# WX0_011_105DL.net
KiCad netlist of a schematic drawn in Altium Designer
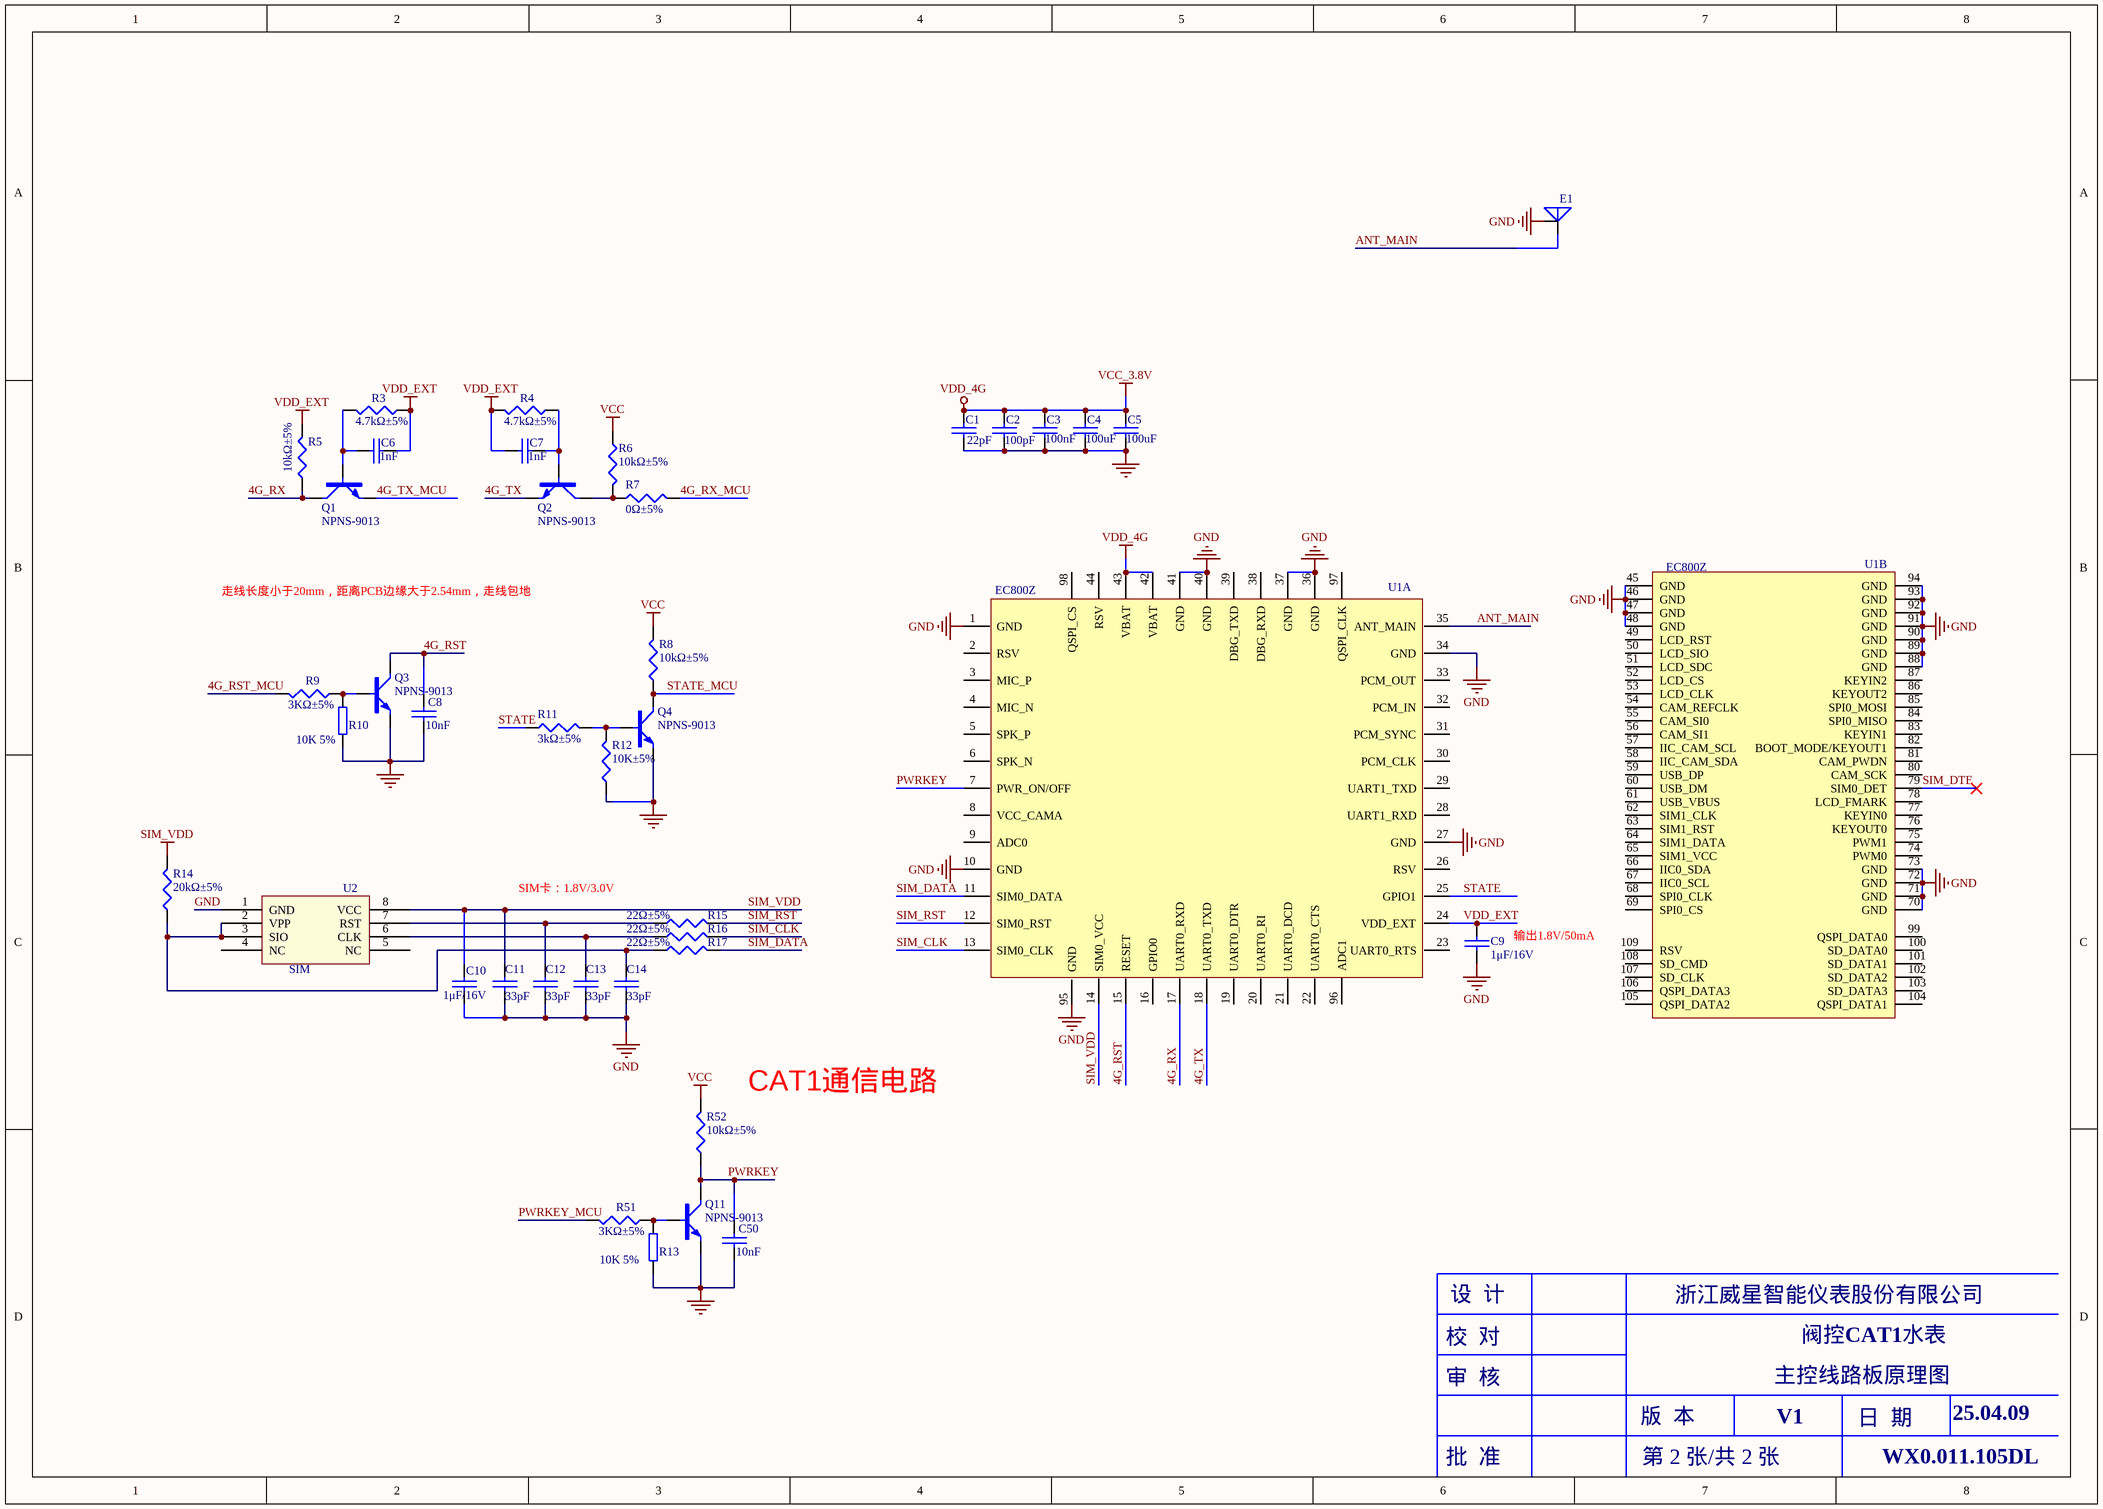
[diagram p0: WX0.011.105DL.SchDoc]

(export (version "E")
  (design (tool "Eeschema 10.0.6"))
  (components
    (comp (ref "C1")
      (value "22pF")
      (footprint "CAP0603")
      (description "贴片电容,22pF±5%/50V,NP0,国巨")
      (fields (field (name "PART NUMBER") "101020103-0009") (field (name "MANUFACTURER") "国巨"))
      (libsource (lib "Devices") (part "CAP"))
    )
    (comp (ref "C2")
      (value "100pF")
      (footprint "CAP0603")
      (description "贴片电容,100pF±10%/50V,NP0,国巨")
      (fields (field (name "PART NUMBER") "101020103-0010") (field (name "MANUFACTURER") "国巨"))
      (libsource (lib "Devices") (part "CAP"))
    )
    (comp (ref "C3")
      (value "100nF")
      (footprint "CAP0603")
      (description "贴片电容,100nF±10%/50V,X7R,国巨")
      (fields (field (name "PART NUMBER") "101020103-0021") (field (name "MANUFACTURER") "国巨"))
      (libsource (lib "Devices") (part "CAP"))
    )
    (comp (ref "C4")
      (value "100uF")
      (footprint "GRM1206")
      (description "贴片电容,100uF±20%/6.3V,X5R,村田")
      (fields (field (name "PART NUMBER") "101020101-0020") (field (name "MANUFACTURER") "村田"))
      (libsource (lib "Devices") (part "CAP"))
    )
    (comp (ref "C5")
      (value "100uF")
      (footprint "GRM1206")
      (description "贴片电容,100uF±20%/6.3V,X5R,村田")
      (fields (field (name "PART NUMBER") "101020101-0020") (field (name "MANUFACTURER") "村田"))
      (libsource (lib "Devices") (part "CAP"))
    )
    (comp (ref "C6")
      (value "1nF")
      (footprint "CAP0603")
      (description "贴片电容,1nF±10%/50V,X7R,国巨")
      (fields (field (name "PART NUMBER") "101020103-0022") (field (name "MANUFACTURER") "国巨"))
      (libsource (lib "Devices") (part "CAP"))
    )
    (comp (ref "C7")
      (value "1nF")
      (footprint "CAP0603")
      (description "贴片电容,1nF±10%/50V,X7R,国巨")
      (fields (field (name "PART NUMBER") "101020103-0022") (field (name "MANUFACTURER") "国巨"))
      (libsource (lib "Devices") (part "CAP"))
    )
    (comp (ref "C8")
      (value "10nF")
      (footprint "CAP0603")
      (description "贴片电容,10nF±10%/50V,X7R,国巨")
      (fields (field (name "PART NUMBER") "101020103-0007") (field (name "MANUFACTURER") "国巨"))
      (libsource (lib "Devices") (part "CAP"))
    )
    (comp (ref "C9")
      (value "1μF/16V")
      (footprint "CAP0603")
      (description "贴片电容,1μF±10%/16V,X7R,国巨")
      (fields (field (name "PART NUMBER") "101020103-0003") (field (name "MANUFACTURER") "国巨"))
      (libsource (lib "Devices") (part "CAP"))
    )
    (comp (ref "C10")
      (value "1μF/16V")
      (footprint "CAP0603")
      (description "贴片电容,1μF±10%/16V,X7R,国巨")
      (fields (field (name "PART NUMBER") "101020103-0003") (field (name "MANUFACTURER") "国巨"))
      (libsource (lib "Devices") (part "CAP"))
    )
    (comp (ref "C11")
      (value "33pF")
      (footprint "CAP0603")
      (description "贴片电容,33pF±10%/50V,NP0,国巨")
      (fields (field (name "PART NUMBER") "101020103-0027") (field (name "MANUFACTURER") "国巨"))
      (libsource (lib "Devices") (part "CAP"))
    )
    (comp (ref "C12")
      (value "33pF")
      (footprint "CAP0603")
      (description "贴片电容,33pF±10%/50V,NP0,国巨")
      (fields (field (name "PART NUMBER") "101020103-0027") (field (name "MANUFACTURER") "国巨"))
      (libsource (lib "Devices") (part "CAP"))
    )
    (comp (ref "C13")
      (value "33pF")
      (footprint "CAP0603")
      (description "贴片电容,33pF±10%/50V,NP0,国巨")
      (fields (field (name "PART NUMBER") "101020103-0027") (field (name "MANUFACTURER") "国巨"))
      (libsource (lib "Devices") (part "CAP"))
    )
    (comp (ref "C14")
      (value "33pF")
      (footprint "CAP0603")
      (description "贴片电容,33pF±10%/50V,NP0,国巨")
      (fields (field (name "PART NUMBER") "101020103-0027") (field (name "MANUFACTURER") "国巨"))
      (libsource (lib "Devices") (part "CAP"))
    )
    (comp (ref "C50")
      (value "10nF")
      (footprint "CAP0603")
      (description "贴片电容,10nF±10%/50V,X7R,国巨")
      (fields (field (name "PART NUMBER") "101020103-0007") (field (name "MANUFACTURER") "国巨"))
      (libsource (lib "Devices") (part "CAP"))
    )
    (comp (ref "E1")
      (value "ANTENNA_3")
      (footprint "天线")
      (description "外置天线焊盘（固定孔）")
      (libsource (lib "Devices") (part "ANTENNA_3"))
    )
    (comp (ref "Q1")
      (value "NPNS-9013")
      (footprint "SOT-23")
      (description "9013,NPN,SOT-23,长电,S9013")
      (fields (field (name "PART NUMBER") "101040201-0002"))
      (libsource (lib "Database_Libs2") (part "03_NPNS-9013"))
    )
    (comp (ref "Q2")
      (value "NPNS-9013")
      (footprint "SOT-23")
      (description "9013,NPN,SOT-23,长电,S9013")
      (fields (field (name "PART NUMBER") "101040201-0002"))
      (libsource (lib "Database_Libs2") (part "03_NPNS-9013"))
    )
    (comp (ref "Q3")
      (value "NPNS-9013")
      (footprint "SOT-23")
      (description "9013,NPN,SOT-23,长电,S9013")
      (fields (field (name "PART NUMBER") "101040201-0002"))
      (libsource (lib "Database_Libs2") (part "03_NPNS-9013"))
    )
    (comp (ref "Q4")
      (value "NPNS-9013")
      (footprint "SOT-23")
      (description "9013,NPN,SOT-23,长电,S9013")
      (fields (field (name "PART NUMBER") "101040201-0002"))
      (libsource (lib "Database_Libs2") (part "03_NPNS-9013"))
    )
    (comp (ref "Q11")
      (value "NPNS-9013")
      (footprint "SOT-23")
      (description "9013,NPN,SOT-23,长电,S9013")
      (fields (field (name "PART NUMBER") "101040201-0002"))
      (libsource (lib "Database_Libs2") (part "03_NPNS-9013"))
    )
    (comp (ref "R3")
      (value "4.7kΩ±5%")
      (footprint "RES0603")
      (description "贴片电阻,4.7kΩ±5%,1/10W,100ppm/℃,国巨")
      (fields (field (name "PART NUMBER") "101010103-0042") (field (name "MANUFACTURER") "国巨"))
      (libsource (lib "Devices") (part "RES1"))
    )
    (comp (ref "R4")
      (value "4.7kΩ±5%")
      (footprint "RES0603")
      (description "贴片电阻,4.7kΩ±5%,1/10W,100ppm/℃,国巨")
      (fields (field (name "PART NUMBER") "101010103-0042") (field (name "MANUFACTURER") "国巨"))
      (libsource (lib "Devices") (part "RES1"))
    )
    (comp (ref "R5")
      (value "10kΩ±5%")
      (footprint "RES0603")
      (description "贴片电阻,10kΩ±5%,1/10W,100ppm/℃,国巨")
      (fields (field (name "PART NUMBER") "101010103-0003") (field (name "MANUFACTURER") "国巨"))
      (libsource (lib "Devices") (part "RES1"))
    )
    (comp (ref "R6")
      (value "10kΩ±5%")
      (footprint "RES0603")
      (description "贴片电阻,10kΩ±5%,1/10W,100ppm/℃,国巨")
      (fields (field (name "PART NUMBER") "101010103-0003") (field (name "MANUFACTURER") "国巨"))
      (libsource (lib "Devices") (part "RES1"))
    )
    (comp (ref "R7")
      (value "0Ω±5%")
      (footprint "RES0603")
      (description "贴片电阻,0Ω±5%,1/10W,100ppm/℃,国巨")
      (fields (field (name "PART NUMBER") "101010103-0001") (field (name "MANUFACTURER") "国巨"))
      (libsource (lib "Devices") (part "RES1"))
    )
    (comp (ref "R8")
      (value "10kΩ±5%")
      (footprint "RES0603")
      (description "贴片电阻,10kΩ±5%,1/10W,100ppm/℃,国巨")
      (fields (field (name "PART NUMBER") "101010103-0003") (field (name "MANUFACTURER") "国巨"))
      (libsource (lib "Devices") (part "RES1"))
    )
    (comp (ref "R9")
      (value "3KΩ±5%")
      (footprint "RES0603")
      (description "贴片电阻,4.7kΩ±5%,1/10W,100ppm/℃,国巨")
      (fields (field (name "PART NUMBER") "101010103-0042") (field (name "MANUFACTURER") "国巨"))
      (libsource (lib "Devices") (part "RES1"))
    )
    (comp (ref "R10")
      (value "10K 5%")
      (footprint "RES0603")
      (description "国巨,±5%,0603,,155 ℃,-55 ℃,RC0603JR-0710KL,无铅,200 ppm/℃,1/10W,,10K")
      (fields (field (name "PART NUMBER") "101010103-0003"))
      (libsource (lib "Database_Libs2") (part "RC03J_10K"))
    )
    (comp (ref "R11")
      (value "3kΩ±5%")
      (footprint "RES0603")
      (description "贴片电阻,4.7kΩ±5%,1/10W,100ppm/℃,国巨")
      (fields (field (name "PART NUMBER") "101010103-0042") (field (name "MANUFACTURER") "国巨"))
      (libsource (lib "Devices") (part "RES1"))
    )
    (comp (ref "R12")
      (value "10K±5%")
      (footprint "RES0603")
      (description "贴片电阻，47K,±5%,1/10W,0603,国巨,RC0603JR-0747KL")
      (fields (field (name "PART NUMBER") "101010103-0012") (field (name "MANUFACTURER") "国巨"))
      (libsource (lib "Devices") (part "RES1"))
    )
    (comp (ref "R13")
      (value "10K 5%")
      (footprint "RES0603")
      (description "国巨,±5%,0603,,155 ℃,-55 ℃,RC0603JR-0710KL,无铅,200 ppm/℃,1/10W,,10K")
      (fields (field (name "PART NUMBER") "101010103-0003"))
      (libsource (lib "Database_Libs2") (part "RC03J_10K"))
    )
    (comp (ref "R14")
      (value "20kΩ±5%")
      (footprint "RES0603")
      (description "贴片电阻,4.7kΩ±5%,1/10W,100ppm/℃,国巨")
      (fields (field (name "PART NUMBER") "101010103-0042") (field (name "MANUFACTURER") "国巨"))
      (libsource (lib "Devices") (part "RES1"))
    )
    (comp (ref "R15")
      (value "22Ω±5%")
      (footprint "RES0603")
      (description "贴片电阻,22Ω±5%,1/10W,100ppm/℃,国巨")
      (fields (field (name "PART NUMBER") "101010103-0009") (field (name "MANUFACTURER") "国巨"))
      (libsource (lib "Devices") (part "RES1"))
    )
    (comp (ref "R16")
      (value "22Ω±5%")
      (footprint "RES0603")
      (description "贴片电阻,22Ω±5%,1/10W,100ppm/℃,国巨")
      (fields (field (name "PART NUMBER") "101010103-0009") (field (name "MANUFACTURER") "国巨"))
      (libsource (lib "Database_Libs2") (part "RES1"))
    )
    (comp (ref "R17")
      (value "22Ω±5%")
      (footprint "RES0603")
      (description "贴片电阻,22Ω±5%,1/10W,100ppm/℃,国巨")
      (fields (field (name "PART NUMBER") "101010103-0009") (field (name "MANUFACTURER") "国巨"))
      (libsource (lib "Devices") (part "RES1"))
    )
    (comp (ref "R51")
      (value "3KΩ±5%")
      (footprint "RES0603")
      (description "贴片电阻,4.7kΩ±5%,1/10W,100ppm/℃,国巨")
      (fields (field (name "PART NUMBER") "101010103-0042") (field (name "MANUFACTURER") "国巨"))
      (libsource (lib "Devices") (part "RES1"))
    )
    (comp (ref "R52")
      (value "10kΩ±5%")
      (footprint "RES0603")
      (description "贴片电阻,10kΩ±5%,1/10W,100ppm/℃,国巨")
      (fields (field (name "PART NUMBER") "101010103-0003") (field (name "MANUFACTURER") "国巨"))
      (libsource (lib "Devices") (part "RES1"))
    )
    (comp (ref "U1")
      (value "EC800Z")
      (footprint "MOD_ML307X_LGA109P")
      (description "集成电路,中国移动，ML307R")
      (fields (field (name "MANUFACTURER") "中国移动"))
      (libsource (lib "Devices") (part "MOD_ML307X_LGA109P"))
    )
    (comp (ref "U2")
      (value "SIM")
      (footprint "SIMIC")
      (description "集成电路,ESIM,杭州电信")
      (fields (field (name "PART NUMBER") "101050101-0120") (field (name "MANUFACTURER") "电信"))
      (libsource (lib "Devices") (part "ESIM"))
    )
  )
  (nets
    (net (code "1") (name "/4G_RST") (class "Default")
      (node (ref "C8") (pin "2") (pinfunction "2_2") (pintype "passive"))
      (node (ref "Q3") (pin "3") (pinfunction "C_3") (pintype "passive"))
      (node (ref "U1") (pin "15") (pinfunction "RESET_15") (pintype "passive"))
    )
    (net (code "2") (name "/4G_RST_MCU") (class "Default")
      (node (ref "R9") (pin "2") (pinfunction "2_2") (pintype "passive"))
    )
    (net (code "3") (name "/4G_RX") (class "Default")
      (node (ref "Q1") (pin "3") (pinfunction "C_3") (pintype "passive"))
      (node (ref "R5") (pin "1") (pinfunction "1_1") (pintype "passive"))
      (node (ref "U1") (pin "17") (pinfunction "UART0_RXD_17") (pintype "passive"))
    )
    (net (code "4") (name "/4G_RX_MCU") (class "Default")
      (node (ref "R7") (pin "2") (pinfunction "2_2") (pintype "passive"))
    )
    (net (code "5") (name "/4G_TX") (class "Default")
      (node (ref "Q2") (pin "2") (pinfunction "E_2") (pintype "passive"))
      (node (ref "U1") (pin "18") (pinfunction "UART0_TXD_18") (pintype "passive"))
    )
    (net (code "6") (name "/4G_TX_MCU") (class "Default")
      (node (ref "Q1") (pin "2") (pinfunction "E_2") (pintype "passive"))
    )
    (net (code "7") (name "/ANT_MAIN") (class "Default")
      (node (ref "E1") (pin "1") (pinfunction "A_1") (pintype "passive"))
      (node (ref "U1") (pin "35") (pinfunction "ANT_MAIN_35") (pintype "passive"))
    )
    (net (code "8") (name "/PWRKEY") (class "Default")
      (node (ref "C50") (pin "2") (pinfunction "2_2") (pintype "passive"))
      (node (ref "Q11") (pin "3") (pinfunction "C_3") (pintype "passive"))
      (node (ref "R52") (pin "1") (pinfunction "1_1") (pintype "passive"))
      (node (ref "U1") (pin "7") (pinfunction "PWR_ON/OFF_7") (pintype "passive"))
    )
    (net (code "9") (name "/PWRKEY_MCU") (class "Default")
      (node (ref "R51") (pin "2") (pinfunction "2_2") (pintype "passive"))
    )
    (net (code "10") (name "/SIM_CLK") (class "Default")
      (node (ref "R16") (pin "2") (pinfunction "2_2") (pintype "passive"))
      (node (ref "U1") (pin "13") (pinfunction "SIM0_CLK_13") (pintype "passive"))
    )
    (net (code "11") (name "/SIM_DATA") (class "Default")
      (node (ref "R17") (pin "2") (pinfunction "2_2") (pintype "passive"))
      (node (ref "U1") (pin "11") (pinfunction "SIM0_DATA_11") (pintype "passive"))
    )
    (net (code "12") (name "/SIM_DTE") (class "Default")
      (node (ref "U1") (pin "79") (pinfunction "SIM0_DET_79") (pintype "passive+no_connect"))
    )
    (net (code "13") (name "/SIM_RST") (class "Default")
      (node (ref "R15") (pin "2") (pinfunction "2_2") (pintype "passive"))
      (node (ref "U1") (pin "12") (pinfunction "SIM0_RST_12") (pintype "passive"))
    )
    (net (code "14") (name "/STATE") (class "Default")
      (node (ref "R11") (pin "1") (pinfunction "1_1") (pintype "passive"))
      (node (ref "U1") (pin "25") (pinfunction "GPIO1_25") (pintype "passive"))
    )
    (net (code "15") (name "/STATE_MCU") (class "Default")
      (node (ref "Q4") (pin "3") (pinfunction "C_3") (pintype "passive"))
      (node (ref "R8") (pin "1") (pinfunction "1_1") (pintype "passive"))
    )
    (net (code "16") (name "GND") (class "Default")
      (node (ref "C1") (pin "1") (pinfunction "1_1") (pintype "passive"))
      (node (ref "C10") (pin "1") (pinfunction "1_1") (pintype "passive"))
      (node (ref "C11") (pin "1") (pinfunction "1_1") (pintype "passive"))
      (node (ref "C12") (pin "1") (pinfunction "1_1") (pintype "passive"))
      (node (ref "C13") (pin "1") (pinfunction "1_1") (pintype "passive"))
      (node (ref "C14") (pin "1") (pinfunction "1_1") (pintype "passive"))
      (node (ref "C2") (pin "1") (pinfunction "1_1") (pintype "passive"))
      (node (ref "C3") (pin "1") (pinfunction "1_1") (pintype "passive"))
      (node (ref "C4") (pin "1") (pinfunction "1_1") (pintype "passive"))
      (node (ref "C5") (pin "1") (pinfunction "1_1") (pintype "passive"))
      (node (ref "C50") (pin "1") (pinfunction "1_1") (pintype "passive"))
      (node (ref "C8") (pin "1") (pinfunction "1_1") (pintype "passive"))
      (node (ref "C9") (pin "1") (pinfunction "1_1") (pintype "passive"))
      (node (ref "E1") (pin "2") (pinfunction "2_2") (pintype "passive"))
      (node (ref "Q11") (pin "2") (pinfunction "E_2") (pintype "passive"))
      (node (ref "Q3") (pin "2") (pinfunction "E_2") (pintype "passive"))
      (node (ref "Q4") (pin "2") (pinfunction "E_2") (pintype "passive"))
      (node (ref "R10") (pin "1") (pinfunction "1_1") (pintype "passive"))
      (node (ref "R12") (pin "1") (pinfunction "1_1") (pintype "passive"))
      (node (ref "R13") (pin "1") (pinfunction "1_1") (pintype "passive"))
      (node (ref "U1") (pin "1") (pinfunction "GND_1") (pintype "passive"))
      (node (ref "U1") (pin "10") (pinfunction "GND_10") (pintype "passive"))
      (node (ref "U1") (pin "27") (pinfunction "GND_27") (pintype "passive"))
      (node (ref "U1") (pin "34") (pinfunction "GND_34") (pintype "passive"))
      (node (ref "U1") (pin "36") (pinfunction "GND_36") (pintype "passive"))
      (node (ref "U1") (pin "37") (pinfunction "GND_37") (pintype "passive"))
      (node (ref "U1") (pin "40") (pinfunction "GND_40") (pintype "passive"))
      (node (ref "U1") (pin "41") (pinfunction "GND_41") (pintype "passive"))
      (node (ref "U1") (pin "45") (pinfunction "GND_45") (pintype "passive"))
      (node (ref "U1") (pin "46") (pinfunction "GND_46") (pintype "passive"))
      (node (ref "U1") (pin "47") (pinfunction "GND_47") (pintype "passive"))
      (node (ref "U1") (pin "48") (pinfunction "GND_48") (pintype "passive"))
      (node (ref "U1") (pin "70") (pinfunction "GND_70") (pintype "passive"))
      (node (ref "U1") (pin "71") (pinfunction "GND_71") (pintype "passive"))
      (node (ref "U1") (pin "72") (pinfunction "GND_72") (pintype "passive"))
      (node (ref "U1") (pin "73") (pinfunction "GND_73") (pintype "passive"))
      (node (ref "U1") (pin "88") (pinfunction "GND_88") (pintype "passive"))
      (node (ref "U1") (pin "89") (pinfunction "GND_89") (pintype "passive"))
      (node (ref "U1") (pin "90") (pinfunction "GND_90") (pintype "passive"))
      (node (ref "U1") (pin "91") (pinfunction "GND_91") (pintype "passive"))
      (node (ref "U1") (pin "92") (pinfunction "GND_92") (pintype "passive"))
      (node (ref "U1") (pin "93") (pinfunction "GND_93") (pintype "passive"))
      (node (ref "U1") (pin "94") (pinfunction "GND_94") (pintype "passive"))
      (node (ref "U1") (pin "95") (pinfunction "GND_95") (pintype "passive"))
      (node (ref "U2") (pin "1") (pinfunction "GND_1") (pintype "passive"))
    )
    (net (code "17") (name "Net-(Q1-B)") (class "Default")
      (node (ref "C6") (pin "1") (pinfunction "1_1") (pintype "passive"))
      (node (ref "Q1") (pin "1") (pinfunction "B_1") (pintype "passive"))
      (node (ref "R3") (pin "2") (pinfunction "2_2") (pintype "passive"))
    )
    (net (code "18") (name "Net-(Q2-B)") (class "Default")
      (node (ref "C7") (pin "2") (pinfunction "2_2") (pintype "passive"))
      (node (ref "Q2") (pin "1") (pinfunction "B_1") (pintype "passive"))
      (node (ref "R4") (pin "1") (pinfunction "1_1") (pintype "passive"))
    )
    (net (code "19") (name "Net-(Q2-C)") (class "Default")
      (node (ref "Q2") (pin "3") (pinfunction "C_3") (pintype "passive"))
      (node (ref "R6") (pin "2") (pinfunction "2_2") (pintype "passive"))
      (node (ref "R7") (pin "1") (pinfunction "1_1") (pintype "passive"))
    )
    (net (code "20") (name "Net-(Q3-B)") (class "Default")
      (node (ref "Q3") (pin "1") (pinfunction "B_1") (pintype "passive"))
      (node (ref "R10") (pin "2") (pinfunction "2_2") (pintype "passive"))
      (node (ref "R9") (pin "1") (pinfunction "1_1") (pintype "passive"))
    )
    (net (code "21") (name "Net-(Q4-B)") (class "Default")
      (node (ref "Q4") (pin "1") (pinfunction "B_1") (pintype "passive"))
      (node (ref "R11") (pin "2") (pinfunction "2_2") (pintype "passive"))
      (node (ref "R12") (pin "2") (pinfunction "2_2") (pintype "passive"))
    )
    (net (code "22") (name "Net-(Q11-B)") (class "Default")
      (node (ref "Q11") (pin "1") (pinfunction "B_1") (pintype "passive"))
      (node (ref "R13") (pin "2") (pinfunction "2_2") (pintype "passive"))
      (node (ref "R51") (pin "1") (pinfunction "1_1") (pintype "passive"))
    )
    (net (code "23") (name "Net-(U2-CLK)") (class "Default")
      (node (ref "C13") (pin "2") (pinfunction "2_2") (pintype "passive"))
      (node (ref "R16") (pin "1") (pinfunction "1_1") (pintype "passive"))
      (node (ref "U2") (pin "6") (pinfunction "CLK_6") (pintype "passive"))
    )
    (net (code "24") (name "Net-(U2-RST)") (class "Default")
      (node (ref "C12") (pin "2") (pinfunction "2_2") (pintype "passive"))
      (node (ref "R15") (pin "1") (pinfunction "1_1") (pintype "passive"))
      (node (ref "U2") (pin "7") (pinfunction "RST_7") (pintype "passive"))
    )
    (net (code "25") (name "Net-(U2-SIO)") (class "Default")
      (node (ref "C14") (pin "2") (pinfunction "2_2") (pintype "passive"))
      (node (ref "R14") (pin "1") (pinfunction "1_1") (pintype "passive"))
      (node (ref "R17") (pin "1") (pinfunction "1_1") (pintype "passive"))
      (node (ref "U2") (pin "2") (pinfunction "VPP_2") (pintype "passive"))
      (node (ref "U2") (pin "3") (pinfunction "SIO_3") (pintype "passive"))
    )
    (net (code "26") (name "SIM_VDD") (class "Default")
      (node (ref "C10") (pin "2") (pinfunction "2_2") (pintype "passive"))
      (node (ref "C11") (pin "2") (pinfunction "2_2") (pintype "passive"))
      (node (ref "R14") (pin "2") (pinfunction "2_2") (pintype "passive"))
      (node (ref "U1") (pin "14") (pinfunction "SIM0_VCC_14") (pintype "passive"))
      (node (ref "U2") (pin "8") (pinfunction "VCC_8") (pintype "passive"))
    )
    (net (code "27") (name "VCC") (class "Default")
      (node (ref "R52") (pin "2") (pinfunction "2_2") (pintype "passive"))
      (node (ref "R6") (pin "1") (pinfunction "1_1") (pintype "passive"))
      (node (ref "R8") (pin "2") (pinfunction "2_2") (pintype "passive"))
    )
    (net (code "28") (name "VCC_3.8V") (class "Default")
      (node (ref "C1") (pin "2") (pinfunction "2_2") (pintype "passive"))
      (node (ref "C2") (pin "2") (pinfunction "2_2") (pintype "passive"))
      (node (ref "C3") (pin "2") (pinfunction "2_2") (pintype "passive"))
      (node (ref "C4") (pin "2") (pinfunction "2_2") (pintype "passive"))
      (node (ref "C5") (pin "2") (pinfunction "2_2") (pintype "passive"))
      (node (ref "U1") (pin "42") (pinfunction "VBAT_42") (pintype "passive"))
      (node (ref "U1") (pin "43") (pinfunction "VBAT_43") (pintype "passive"))
    )
    (net (code "29") (name "VDD_EXT") (class "Default")
      (node (ref "C6") (pin "2") (pinfunction "2_2") (pintype "passive"))
      (node (ref "C7") (pin "1") (pinfunction "1_1") (pintype "passive"))
      (node (ref "C9") (pin "2") (pinfunction "2_2") (pintype "passive"))
      (node (ref "R3") (pin "1") (pinfunction "1_1") (pintype "passive"))
      (node (ref "R4") (pin "2") (pinfunction "2_2") (pintype "passive"))
      (node (ref "R5") (pin "2") (pinfunction "2_2") (pintype "passive"))
      (node (ref "U1") (pin "24") (pinfunction "VDD_EXT_24") (pintype "passive"))
    )
    (net (code "30") (name "unconnected-(U1A-ADC0-Pad9)") (class "Default")
      (node (ref "U1") (pin "9") (pinfunction "ADC0_9") (pintype "passive"))
    )
    (net (code "31") (name "unconnected-(U1A-ADC1-Pad96)") (class "Default")
      (node (ref "U1") (pin "96") (pinfunction "ADC1_96") (pintype "passive"))
    )
    (net (code "32") (name "unconnected-(U1A-DBG_RXD-Pad38)") (class "Default")
      (node (ref "U1") (pin "38") (pinfunction "DBG_RXD_38") (pintype "passive"))
    )
    (net (code "33") (name "unconnected-(U1A-DBG_TXD-Pad39)") (class "Default")
      (node (ref "U1") (pin "39") (pinfunction "DBG_TXD_39") (pintype "passive"))
    )
    (net (code "34") (name "unconnected-(U1A-GPIO0-Pad16)") (class "Default")
      (node (ref "U1") (pin "16") (pinfunction "GPIO0_16") (pintype "passive"))
    )
    (net (code "35") (name "unconnected-(U1A-MIC_N-Pad4)") (class "Default")
      (node (ref "U1") (pin "4") (pinfunction "MIC_N_4") (pintype "passive"))
    )
    (net (code "36") (name "unconnected-(U1A-MIC_P-Pad3)") (class "Default")
      (node (ref "U1") (pin "3") (pinfunction "MIC_P_3") (pintype "passive"))
    )
    (net (code "37") (name "unconnected-(U1A-PCM_CLK-Pad30)") (class "Default")
      (node (ref "U1") (pin "30") (pinfunction "PCM_CLK_30") (pintype "passive"))
    )
    (net (code "38") (name "unconnected-(U1A-PCM_IN-Pad32)") (class "Default")
      (node (ref "U1") (pin "32") (pinfunction "PCM_IN_32") (pintype "passive"))
    )
    (net (code "39") (name "unconnected-(U1A-PCM_OUT-Pad33)") (class "Default")
      (node (ref "U1") (pin "33") (pinfunction "PCM_OUT_33") (pintype "passive"))
    )
    (net (code "40") (name "unconnected-(U1A-PCM_SYNC-Pad31)") (class "Default")
      (node (ref "U1") (pin "31") (pinfunction "PCM_SYNC_31") (pintype "passive"))
    )
    (net (code "41") (name "unconnected-(U1A-QSPI_CLK-Pad97)") (class "Default")
      (node (ref "U1") (pin "97") (pinfunction "QSPI_CLK_97") (pintype "passive"))
    )
    (net (code "42") (name "unconnected-(U1A-QSPI_CS-Pad98)") (class "Default")
      (node (ref "U1") (pin "98") (pinfunction "QSPI_CS_98") (pintype "passive"))
    )
    (net (code "43") (name "unconnected-(U1A-RSV-Pad2)") (class "Default")
      (node (ref "U1") (pin "2") (pinfunction "RSV_2") (pintype "passive"))
    )
    (net (code "44") (name "unconnected-(U1A-RSV-Pad26)") (class "Default")
      (node (ref "U1") (pin "26") (pinfunction "RSV_26") (pintype "passive"))
    )
    (net (code "45") (name "unconnected-(U1A-RSV-Pad44)") (class "Default")
      (node (ref "U1") (pin "44") (pinfunction "RSV_44") (pintype "passive"))
    )
    (net (code "46") (name "unconnected-(U1A-SPK_N-Pad6)") (class "Default")
      (node (ref "U1") (pin "6") (pinfunction "SPK_N_6") (pintype "passive"))
    )
    (net (code "47") (name "unconnected-(U1A-SPK_P-Pad5)") (class "Default")
      (node (ref "U1") (pin "5") (pinfunction "SPK_P_5") (pintype "passive"))
    )
    (net (code "48") (name "unconnected-(U1A-UART0_CTS-Pad22)") (class "Default")
      (node (ref "U1") (pin "22") (pinfunction "UART0_CTS_22") (pintype "passive"))
    )
    (net (code "49") (name "unconnected-(U1A-UART0_DCD-Pad21)") (class "Default")
      (node (ref "U1") (pin "21") (pinfunction "UART0_DCD_21") (pintype "passive"))
    )
    (net (code "50") (name "unconnected-(U1A-UART0_DTR-Pad19)") (class "Default")
      (node (ref "U1") (pin "19") (pinfunction "UART0_DTR_19") (pintype "passive"))
    )
    (net (code "51") (name "unconnected-(U1A-UART0_RI-Pad20)") (class "Default")
      (node (ref "U1") (pin "20") (pinfunction "UART0_RI_20") (pintype "passive"))
    )
    (net (code "52") (name "unconnected-(U1A-UART0_RTS-Pad23)") (class "Default")
      (node (ref "U1") (pin "23") (pinfunction "UART0_RTS_23") (pintype "passive"))
    )
    (net (code "53") (name "unconnected-(U1A-UART1_RXD-Pad28)") (class "Default")
      (node (ref "U1") (pin "28") (pinfunction "UART1_RXD_28") (pintype "passive"))
    )
    (net (code "54") (name "unconnected-(U1A-UART1_TXD-Pad29)") (class "Default")
      (node (ref "U1") (pin "29") (pinfunction "UART1_TXD_29") (pintype "passive"))
    )
    (net (code "55") (name "unconnected-(U1A-VCC_CAMA-Pad8)") (class "Default")
      (node (ref "U1") (pin "8") (pinfunction "VCC_CAMA_8") (pintype "passive"))
    )
    (net (code "56") (name "unconnected-(U1B-BOOT_MODE{slash}KEYOUT1-Pad82)") (class "Default")
      (node (ref "U1") (pin "82") (pinfunction "BOOT_MODE/KEYOUT1_82") (pintype "passive"))
    )
    (net (code "57") (name "unconnected-(U1B-CAM_PWDN-Pad81)") (class "Default")
      (node (ref "U1") (pin "81") (pinfunction "CAM_PWDN_81") (pintype "passive"))
    )
    (net (code "58") (name "unconnected-(U1B-CAM_REFCLK-Pad54)") (class "Default")
      (node (ref "U1") (pin "54") (pinfunction "CAM_REFCLK_54") (pintype "passive"))
    )
    (net (code "59") (name "unconnected-(U1B-CAM_SCK-Pad80)") (class "Default")
      (node (ref "U1") (pin "80") (pinfunction "CAM_SCK_80") (pintype "passive"))
    )
    (net (code "60") (name "unconnected-(U1B-CAM_SI0-Pad55)") (class "Default")
      (node (ref "U1") (pin "55") (pinfunction "CAM_SI0_55") (pintype "passive"))
    )
    (net (code "61") (name "unconnected-(U1B-CAM_SI1-Pad56)") (class "Default")
      (node (ref "U1") (pin "56") (pinfunction "CAM_SI1_56") (pintype "passive"))
    )
    (net (code "62") (name "unconnected-(U1B-IIC0_SCL-Pad67)") (class "Default")
      (node (ref "U1") (pin "67") (pinfunction "IIC0_SCL_67") (pintype "passive"))
    )
    (net (code "63") (name "unconnected-(U1B-IIC0_SDA-Pad66)") (class "Default")
      (node (ref "U1") (pin "66") (pinfunction "IIC0_SDA_66") (pintype "passive"))
    )
    (net (code "64") (name "unconnected-(U1B-IIC_CAM_SCL-Pad57)") (class "Default")
      (node (ref "U1") (pin "57") (pinfunction "IIC_CAM_SCL_57") (pintype "passive"))
    )
    (net (code "65") (name "unconnected-(U1B-IIC_CAM_SDA-Pad58)") (class "Default")
      (node (ref "U1") (pin "58") (pinfunction "IIC_CAM_SDA_58") (pintype "passive"))
    )
    (net (code "66") (name "unconnected-(U1B-KEYIN0-Pad77)") (class "Default")
      (node (ref "U1") (pin "77") (pinfunction "KEYIN0_77") (pintype "passive"))
    )
    (net (code "67") (name "unconnected-(U1B-KEYIN1-Pad83)") (class "Default")
      (node (ref "U1") (pin "83") (pinfunction "KEYIN1_83") (pintype "passive"))
    )
    (net (code "68") (name "unconnected-(U1B-KEYIN2-Pad87)") (class "Default")
      (node (ref "U1") (pin "87") (pinfunction "KEYIN2_87") (pintype "passive"))
    )
    (net (code "69") (name "unconnected-(U1B-KEYOUT0-Pad76)") (class "Default")
      (node (ref "U1") (pin "76") (pinfunction "KEYOUT0_76") (pintype "passive"))
    )
    (net (code "70") (name "unconnected-(U1B-KEYOUT2-Pad86)") (class "Default")
      (node (ref "U1") (pin "86") (pinfunction "KEYOUT2_86") (pintype "passive"))
    )
    (net (code "71") (name "unconnected-(U1B-LCD_CLK-Pad53)") (class "Default")
      (node (ref "U1") (pin "53") (pinfunction "LCD_CLK_53") (pintype "passive"))
    )
    (net (code "72") (name "unconnected-(U1B-LCD_CS-Pad52)") (class "Default")
      (node (ref "U1") (pin "52") (pinfunction "LCD_CS_52") (pintype "passive"))
    )
    (net (code "73") (name "unconnected-(U1B-LCD_FMARK-Pad78)") (class "Default")
      (node (ref "U1") (pin "78") (pinfunction "LCD_FMARK_78") (pintype "passive"))
    )
    (net (code "74") (name "unconnected-(U1B-LCD_RST-Pad49)") (class "Default")
      (node (ref "U1") (pin "49") (pinfunction "LCD_RST_49") (pintype "passive"))
    )
    (net (code "75") (name "unconnected-(U1B-LCD_SDC-Pad51)") (class "Default")
      (node (ref "U1") (pin "51") (pinfunction "LCD_SDC_51") (pintype "passive"))
    )
    (net (code "76") (name "unconnected-(U1B-LCD_SIO-Pad50)") (class "Default")
      (node (ref "U1") (pin "50") (pinfunction "LCD_SIO_50") (pintype "passive"))
    )
    (net (code "77") (name "unconnected-(U1B-PWM0-Pad74)") (class "Default")
      (node (ref "U1") (pin "74") (pinfunction "PWM0_74") (pintype "passive"))
    )
    (net (code "78") (name "unconnected-(U1B-PWM1-Pad75)") (class "Default")
      (node (ref "U1") (pin "75") (pinfunction "PWM1_75") (pintype "passive"))
    )
    (net (code "79") (name "unconnected-(U1B-QSPI_DATA0-Pad99)") (class "Default")
      (node (ref "U1") (pin "99") (pinfunction "QSPI_DATA0_99") (pintype "passive"))
    )
    (net (code "80") (name "unconnected-(U1B-QSPI_DATA1-Pad104)") (class "Default")
      (node (ref "U1") (pin "104") (pinfunction "QSPI_DATA1_104") (pintype "passive"))
    )
    (net (code "81") (name "unconnected-(U1B-QSPI_DATA2-Pad105)") (class "Default")
      (node (ref "U1") (pin "105") (pinfunction "QSPI_DATA2_105") (pintype "passive"))
    )
    (net (code "82") (name "unconnected-(U1B-QSPI_DATA3-Pad106)") (class "Default")
      (node (ref "U1") (pin "106") (pinfunction "QSPI_DATA3_106") (pintype "passive"))
    )
    (net (code "83") (name "unconnected-(U1B-RSV-Pad109)") (class "Default")
      (node (ref "U1") (pin "109") (pinfunction "RSV_109") (pintype "passive"))
    )
    (net (code "84") (name "unconnected-(U1B-SD_CLK-Pad107)") (class "Default")
      (node (ref "U1") (pin "107") (pinfunction "SD_CLK_107") (pintype "passive"))
    )
    (net (code "85") (name "unconnected-(U1B-SD_CMD-Pad108)") (class "Default")
      (node (ref "U1") (pin "108") (pinfunction "SD_CMD_108") (pintype "passive"))
    )
    (net (code "86") (name "unconnected-(U1B-SD_DATA0-Pad100)") (class "Default")
      (node (ref "U1") (pin "100") (pinfunction "SD_DATA0_100") (pintype "passive"))
    )
    (net (code "87") (name "unconnected-(U1B-SD_DATA1-Pad101)") (class "Default")
      (node (ref "U1") (pin "101") (pinfunction "SD_DATA1_101") (pintype "passive"))
    )
    (net (code "88") (name "unconnected-(U1B-SD_DATA2-Pad102)") (class "Default")
      (node (ref "U1") (pin "102") (pinfunction "SD_DATA2_102") (pintype "passive"))
    )
    (net (code "89") (name "unconnected-(U1B-SD_DATA3-Pad103)") (class "Default")
      (node (ref "U1") (pin "103") (pinfunction "SD_DATA3_103") (pintype "passive"))
    )
    (net (code "90") (name "unconnected-(U1B-SIM1_CLK-Pad62)") (class "Default")
      (node (ref "U1") (pin "62") (pinfunction "SIM1_CLK_62") (pintype "passive"))
    )
    (net (code "91") (name "unconnected-(U1B-SIM1_DATA-Pad64)") (class "Default")
      (node (ref "U1") (pin "64") (pinfunction "SIM1_DATA_64") (pintype "passive"))
    )
    (net (code "92") (name "unconnected-(U1B-SIM1_RST-Pad63)") (class "Default")
      (node (ref "U1") (pin "63") (pinfunction "SIM1_RST_63") (pintype "passive"))
    )
    (net (code "93") (name "unconnected-(U1B-SIM1_VCC-Pad65)") (class "Default")
      (node (ref "U1") (pin "65") (pinfunction "SIM1_VCC_65") (pintype "passive"))
    )
    (net (code "94") (name "unconnected-(U1B-SPI0_CLK-Pad68)") (class "Default")
      (node (ref "U1") (pin "68") (pinfunction "SPI0_CLK_68") (pintype "passive"))
    )
    (net (code "95") (name "unconnected-(U1B-SPI0_CS-Pad69)") (class "Default")
      (node (ref "U1") (pin "69") (pinfunction "SPI0_CS_69") (pintype "passive"))
    )
    (net (code "96") (name "unconnected-(U1B-SPI0_MISO-Pad84)") (class "Default")
      (node (ref "U1") (pin "84") (pinfunction "SPI0_MISO_84") (pintype "passive"))
    )
    (net (code "97") (name "unconnected-(U1B-SPI0_MOSI-Pad85)") (class "Default")
      (node (ref "U1") (pin "85") (pinfunction "SPI0_MOSI_85") (pintype "passive"))
    )
    (net (code "98") (name "unconnected-(U1B-USB_DM-Pad60)") (class "Default")
      (node (ref "U1") (pin "60") (pinfunction "USB_DM_60") (pintype "passive"))
    )
    (net (code "99") (name "unconnected-(U1B-USB_DP-Pad59)") (class "Default")
      (node (ref "U1") (pin "59") (pinfunction "USB_DP_59") (pintype "passive"))
    )
    (net (code "100") (name "unconnected-(U1B-USB_VBUS-Pad61)") (class "Default")
      (node (ref "U1") (pin "61") (pinfunction "USB_VBUS_61") (pintype "passive"))
    )
    (net (code "101") (name "unconnected-(U2-NC-Pad4)") (class "Default")
      (node (ref "U2") (pin "4") (pinfunction "NC_4") (pintype "passive"))
    )
    (net (code "102") (name "unconnected-(U2-NC-Pad5)") (class "Default")
      (node (ref "U2") (pin "5") (pinfunction "NC_5") (pintype "passive"))
    )
  )
)
